# TB6612FNG.net
KiCad netlist of a schematic drawn in EAGLE
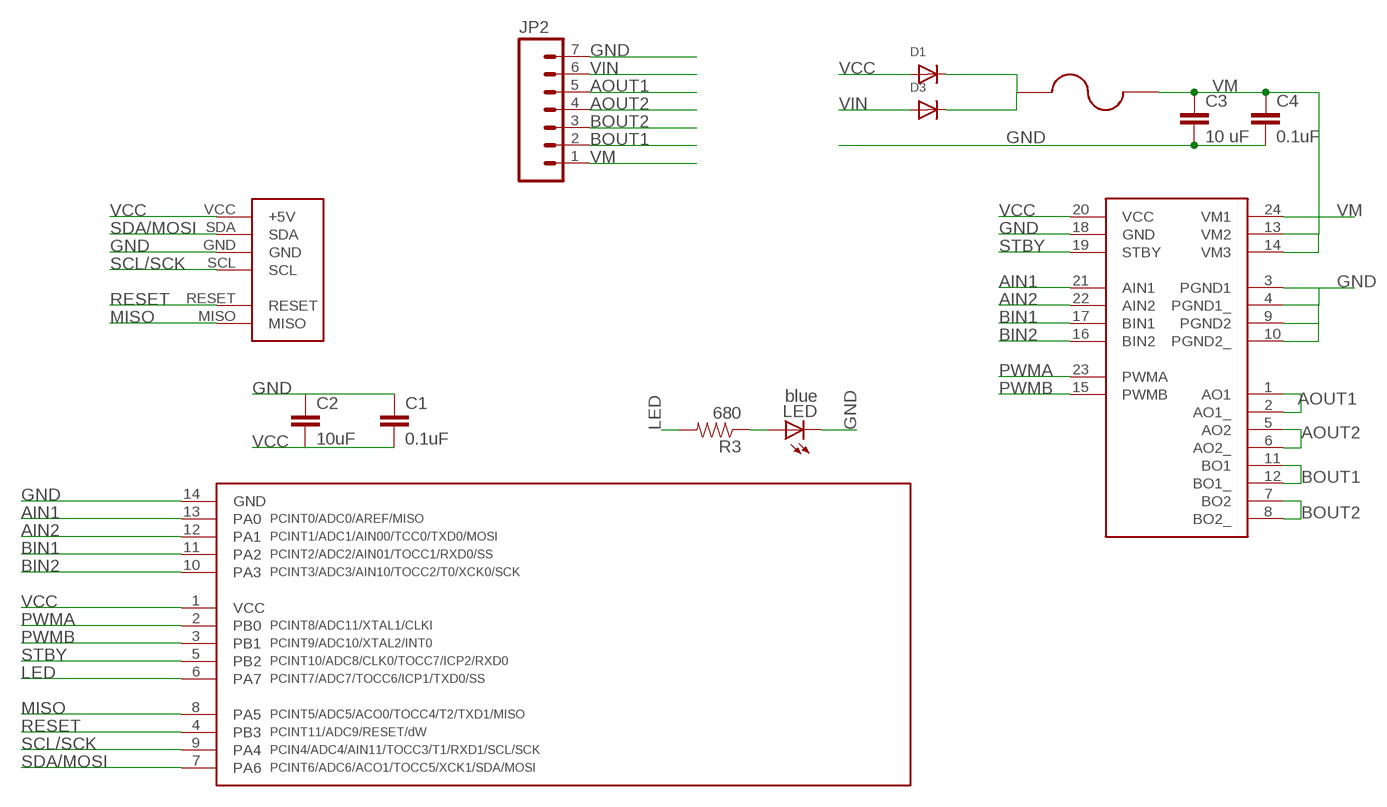
[diagram p0: schematic, sheet 1]

(export (version "E")
  (design (tool "Eeschema 10.0.6"))
  (components
    (comp (ref "C1")
      (value "0.1uF")
      (footprint "eagle-import:0805")
      (libsource (lib "eagle-import") (part "CAP0805"))
    )
    (comp (ref "C2")
      (value "10uF")
      (footprint "eagle-import:0805")
      (libsource (lib "eagle-import") (part "CAP0805"))
    )
    (comp (ref "C3")
      (value "10 uF")
      (footprint "eagle-import:0805")
      (libsource (lib "eagle-import") (part "CAP0805"))
    )
    (comp (ref "C4")
      (value "0.1uF")
      (footprint "eagle-import:0805")
      (libsource (lib "eagle-import") (part "CAP0805"))
    )
    (comp (ref "D1")
      (value "DIODESOD-123")
      (footprint "eagle-import:SOD-123")
      (libsource (lib "eagle-import") (part "DIODESOD-123"))
    )
    (comp (ref "D3")
      (value "DIODESOD-123")
      (footprint "eagle-import:SOD-123")
      (libsource (lib "eagle-import") (part "DIODESOD-123"))
    )
    (comp (ref "JP2")
      (value "M07")
      (footprint "eagle-import:1X07")
      (libsource (lib "eagle-import") (part "M07"))
    )
    (comp (ref "LED")
      (value "blue")
      (footprint "eagle-import:CHIPLED_1206")
      (libsource (lib "eagle-import") (part "LEDCHIPLED_1206"))
    )
    (comp (ref "R3")
      (value "680")
      (footprint "eagle-import:0805")
      (libsource (lib "eagle-import") (part "RESISTOR0805-RES"))
    )
    (comp (ref "U$1")
      (value "TB6612FNG")
      (footprint "eagle-import:SSOP-24")
      (libsource (lib "eagle-import") (part "TB6612FNG"))
    )
    (comp (ref "U$2")
      (value "FUSE")
      (footprint "eagle-import:1812")
      (libsource (lib "eagle-import") (part "FUSE"))
    )
    (comp (ref "U$3")
      (value "TINY841")
      (footprint "eagle-import:SOIC14")
      (libsource (lib "eagle-import") (part "TINY841"))
    )
    (comp (ref "U$4")
      (value "FOOTPRINTFOOTPRINT-2")
      (footprint "eagle-import:FOOTPRINT2")
      (libsource (lib "eagle-import") (part "FOOTPRINTFOOTPRINT-2"))
    )
  )
  (nets
    (net (code "1") (name "/AIN1") (class "Default")
      (node (ref "U$1") (pin "21") (pinfunction "AIN1_21") (pintype "bidirectional"))
      (node (ref "U$3") (pin "13") (pinfunction "PA0_13") (pintype "bidirectional"))
    )
    (net (code "2") (name "/AIN2") (class "Default")
      (node (ref "U$1") (pin "22") (pinfunction "AIN2_22") (pintype "bidirectional"))
      (node (ref "U$3") (pin "12") (pinfunction "PA1_12") (pintype "bidirectional"))
    )
    (net (code "3") (name "/AOUT1") (class "Default")
      (node (ref "JP2") (pin "5") (pinfunction "5_5") (pintype "passive"))
      (node (ref "U$1") (pin "1") (pinfunction "AO1_1") (pintype "bidirectional"))
      (node (ref "U$1") (pin "2") (pinfunction "AO1__2") (pintype "bidirectional"))
    )
    (net (code "4") (name "/AOUT2") (class "Default")
      (node (ref "JP2") (pin "4") (pinfunction "4_4") (pintype "passive"))
      (node (ref "U$1") (pin "5") (pinfunction "AO2_5") (pintype "bidirectional"))
      (node (ref "U$1") (pin "6") (pinfunction "AO2__6") (pintype "bidirectional"))
    )
    (net (code "5") (name "/BIN1") (class "Default")
      (node (ref "U$1") (pin "17") (pinfunction "BIN1_17") (pintype "bidirectional"))
      (node (ref "U$3") (pin "11") (pinfunction "PA2_11") (pintype "bidirectional"))
    )
    (net (code "6") (name "/BIN2") (class "Default")
      (node (ref "U$1") (pin "16") (pinfunction "BIN2_16") (pintype "bidirectional"))
      (node (ref "U$3") (pin "10") (pinfunction "PA3_10") (pintype "bidirectional"))
    )
    (net (code "7") (name "/BOUT1") (class "Default")
      (node (ref "JP2") (pin "2") (pinfunction "2_2") (pintype "passive"))
      (node (ref "U$1") (pin "11") (pinfunction "BO1_11") (pintype "bidirectional"))
      (node (ref "U$1") (pin "12") (pinfunction "BO1__12") (pintype "bidirectional"))
    )
    (net (code "8") (name "/BOUT2") (class "Default")
      (node (ref "JP2") (pin "3") (pinfunction "3_3") (pintype "passive"))
      (node (ref "U$1") (pin "7") (pinfunction "BO2_7") (pintype "bidirectional"))
      (node (ref "U$1") (pin "8") (pinfunction "BO2__8") (pintype "bidirectional"))
    )
    (net (code "9") (name "/GND") (class "Default")
      (node (ref "C1") (pin "1") (pinfunction "1_1") (pintype "passive"))
      (node (ref "C2") (pin "1") (pinfunction "1_1") (pintype "passive"))
      (node (ref "C3") (pin "2") (pinfunction "2_2") (pintype "passive"))
      (node (ref "C4") (pin "2") (pinfunction "2_2") (pintype "passive"))
      (node (ref "JP2") (pin "7") (pinfunction "7_7") (pintype "passive"))
      (node (ref "LED") (pin "C") (pinfunction "C_C") (pintype "passive"))
      (node (ref "U$1") (pin "10") (pinfunction "PGND2__10") (pintype "bidirectional"))
      (node (ref "U$1") (pin "18") (pinfunction "GND_18") (pintype "bidirectional"))
      (node (ref "U$1") (pin "3") (pinfunction "PGND1_3") (pintype "bidirectional"))
      (node (ref "U$1") (pin "4") (pinfunction "PGND1__4") (pintype "bidirectional"))
      (node (ref "U$1") (pin "9") (pinfunction "PGND2_9") (pintype "bidirectional"))
      (node (ref "U$3") (pin "14") (pinfunction "GND_14") (pintype "bidirectional"))
      (node (ref "U$4") (pin "GND") (pinfunction "GND_GND") (pintype "power_in"))
    )
    (net (code "10") (name "/LED") (class "Default")
      (node (ref "R3") (pin "2") (pinfunction "2_2") (pintype "passive"))
      (node (ref "U$3") (pin "6") (pinfunction "PA7_6") (pintype "bidirectional"))
    )
    (net (code "11") (name "/MISO") (class "Default")
      (node (ref "U$3") (pin "8") (pinfunction "PA5_8") (pintype "bidirectional"))
      (node (ref "U$4") (pin "MISO") (pinfunction "MISO_MISO") (pintype "bidirectional"))
    )
    (net (code "12") (name "/PWMA") (class "Default")
      (node (ref "U$1") (pin "23") (pinfunction "PWMA_23") (pintype "bidirectional"))
      (node (ref "U$3") (pin "2") (pinfunction "PB0_2") (pintype "bidirectional"))
    )
    (net (code "13") (name "/PWMB") (class "Default")
      (node (ref "U$1") (pin "15") (pinfunction "PWMB_15") (pintype "bidirectional"))
      (node (ref "U$3") (pin "3") (pinfunction "PB1_3") (pintype "bidirectional"))
    )
    (net (code "14") (name "/RESET") (class "Default")
      (node (ref "U$3") (pin "4") (pinfunction "PB3_4") (pintype "bidirectional"))
      (node (ref "U$4") (pin "RESET") (pinfunction "RESET_RESET") (pintype "bidirectional"))
    )
    (net (code "15") (name "/SCL{slash}SCK") (class "Default")
      (node (ref "U$3") (pin "9") (pinfunction "PA4_9") (pintype "bidirectional"))
      (node (ref "U$4") (pin "SCL") (pinfunction "SCL_SCL") (pintype "bidirectional"))
    )
    (net (code "16") (name "/SDA{slash}MOSI") (class "Default")
      (node (ref "U$3") (pin "7") (pinfunction "PA6_7") (pintype "bidirectional"))
      (node (ref "U$4") (pin "SDA") (pinfunction "SDA_SDA") (pintype "bidirectional"))
    )
    (net (code "17") (name "/STBY") (class "Default")
      (node (ref "U$1") (pin "19") (pinfunction "STBY_19") (pintype "bidirectional"))
      (node (ref "U$3") (pin "5") (pinfunction "PB2_5") (pintype "bidirectional"))
    )
    (net (code "18") (name "/VCC") (class "Default")
      (node (ref "C1") (pin "2") (pinfunction "2_2") (pintype "passive"))
      (node (ref "C2") (pin "2") (pinfunction "2_2") (pintype "passive"))
      (node (ref "D1") (pin "A") (pinfunction "A_A") (pintype "passive"))
      (node (ref "U$1") (pin "20") (pinfunction "VCC_20") (pintype "bidirectional"))
      (node (ref "U$3") (pin "1") (pinfunction "VCC_1") (pintype "bidirectional"))
      (node (ref "U$4") (pin "VCC") (pinfunction "+5V_VCC") (pintype "power_in"))
    )
    (net (code "19") (name "/VIN") (class "Default")
      (node (ref "D3") (pin "A") (pinfunction "A_A") (pintype "passive"))
      (node (ref "JP2") (pin "6") (pinfunction "6_6") (pintype "passive"))
    )
    (net (code "20") (name "/VM") (class "Default")
      (node (ref "C3") (pin "1") (pinfunction "1_1") (pintype "passive"))
      (node (ref "C4") (pin "1") (pinfunction "1_1") (pintype "passive"))
      (node (ref "JP2") (pin "1") (pinfunction "1_1") (pintype "passive"))
      (node (ref "U$1") (pin "13") (pinfunction "VM2_13") (pintype "bidirectional"))
      (node (ref "U$1") (pin "14") (pinfunction "VM3_14") (pintype "bidirectional"))
      (node (ref "U$1") (pin "24") (pinfunction "VM1_24") (pintype "bidirectional"))
      (node (ref "U$2") (pin "P$2") (pinfunction "2_P$2") (pintype "bidirectional"))
    )
    (net (code "21") (name "Net-(LED-PadA)") (class "Default")
      (node (ref "LED") (pin "A") (pinfunction "A_A") (pintype "passive"))
      (node (ref "R3") (pin "1") (pinfunction "1_1") (pintype "passive"))
    )
    (net (code "22") (name "Net-(U$2-1)") (class "Default")
      (node (ref "D1") (pin "C") (pinfunction "C_C") (pintype "passive"))
      (node (ref "D3") (pin "C") (pinfunction "C_C") (pintype "passive"))
      (node (ref "U$2") (pin "P$1") (pinfunction "1_P$1") (pintype "bidirectional"))
    )
  )
)
